# LED_Driver.net
KiCad netlist of a schematic drawn in Altium Designer
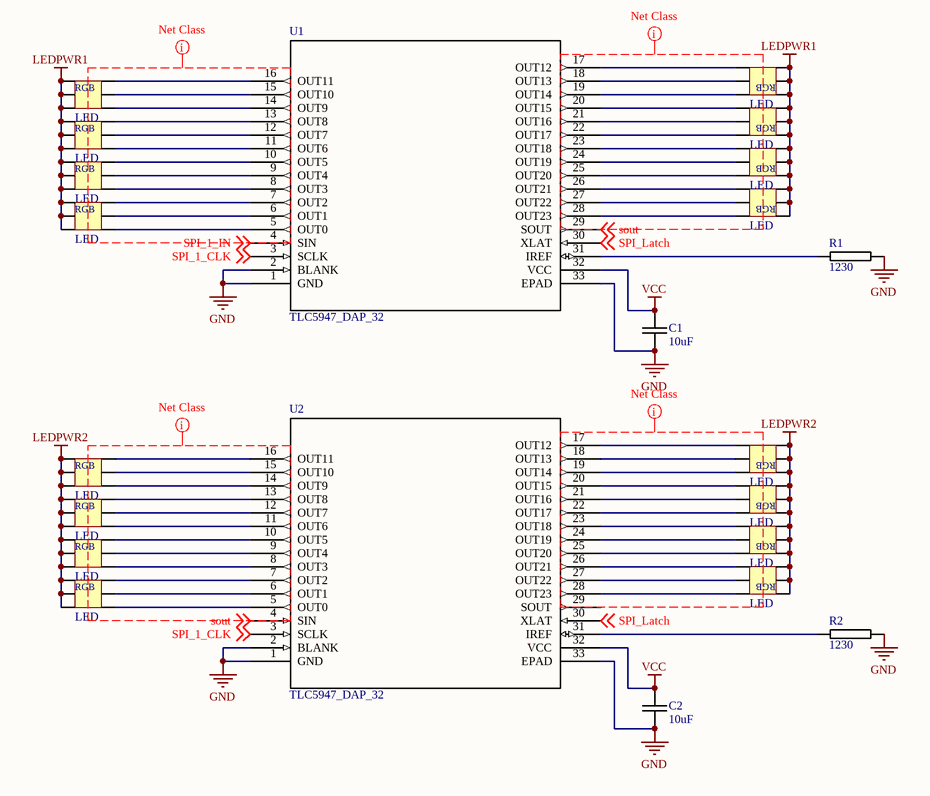
[diagram p0: LED Driver.SchDoc]

(export (version "E")
  (design (tool "Eeschema 10.0.6"))
  (components
    (comp (ref "C1")
      (value "10uF")
      (footprint "0603C-GENERIC")
      (description "CAPACITOR 0603 CERAMIC")
      (fields
        (field (name "MANUFACTURER PART NUMBER") "C1608X5R0J106M")
        (field (name "MANUFACTURER") "TDK Corporation")
      )
      (libsource (lib "vh_altium_library") (part "0603C-10UF-10V-X5R-TDK"))
    )
    (comp (ref "C2")
      (value "10uF")
      (footprint "0603C-GENERIC")
      (description "CAPACITOR 0603 CERAMIC")
      (fields
        (field (name "MANUFACTURER PART NUMBER") "C1608X5R0J106M")
        (field (name "MANUFACTURER") "TDK Corporation")
      )
      (libsource (lib "vh_altium_library") (part "0603C-10UF-10V-X5R-TDK"))
    )
    (comp (ref "D1") (value "LED") (footprint "LED-TRICOLOR-5050") (libsource (lib "") (part "RGB LED_1")))
    (comp (ref "D2")
      (value "LED")
      (footprint "LED-TRICOLOR-5050")
      (libsource (lib "2014-04-10_10-38-29") (part "RGB LED"))
    )
    (comp (ref "D3") (value "LED") (footprint "LED-TRICOLOR-5050") (libsource (lib "") (part "RGB LED_1")))
    (comp (ref "D4")
      (value "LED")
      (footprint "LED-TRICOLOR-5050")
      (libsource (lib "2014-04-10_10-38-29") (part "RGB LED"))
    )
    (comp (ref "D5") (value "LED") (footprint "LED-TRICOLOR-5050") (libsource (lib "") (part "RGB LED_1")))
    (comp (ref "D6")
      (value "LED")
      (footprint "LED-TRICOLOR-5050")
      (libsource (lib "2014-04-10_10-38-29") (part "RGB LED"))
    )
    (comp (ref "D7") (value "LED") (footprint "LED-TRICOLOR-5050") (libsource (lib "") (part "RGB LED_1")))
    (comp (ref "D8")
      (value "LED")
      (footprint "LED-TRICOLOR-5050")
      (libsource (lib "2014-04-10_10-38-29") (part "RGB LED"))
    )
    (comp (ref "D9") (value "LED") (footprint "LED-TRICOLOR-5050") (libsource (lib "") (part "RGB LED_1")))
    (comp (ref "D10")
      (value "LED")
      (footprint "LED-TRICOLOR-5050")
      (libsource (lib "2014-04-10_10-38-29") (part "RGB LED"))
    )
    (comp (ref "D11") (value "LED") (footprint "LED-TRICOLOR-5050") (libsource (lib "") (part "RGB LED_1")))
    (comp (ref "D12")
      (value "LED")
      (footprint "LED-TRICOLOR-5050")
      (libsource (lib "2014-04-10_10-38-29") (part "RGB LED"))
    )
    (comp (ref "D13") (value "LED") (footprint "LED-TRICOLOR-5050") (libsource (lib "") (part "RGB LED_1")))
    (comp (ref "D14")
      (value "LED")
      (footprint "LED-TRICOLOR-5050")
      (libsource (lib "2014-04-10_10-38-29") (part "RGB LED"))
    )
    (comp (ref "D15") (value "LED") (footprint "LED-TRICOLOR-5050") (libsource (lib "") (part "RGB LED_1")))
    (comp (ref "D16")
      (value "LED")
      (footprint "LED-TRICOLOR-5050")
      (libsource (lib "2014-04-10_10-38-29") (part "RGB LED"))
    )
    (comp (ref "R1")
      (value "1230")
      (footprint "0603R-TBD")
      (description "RESISTOR 0603 VALUE TO BE DETERMINED")
      (libsource (lib "vh_altium_library") (part "0603R-TBD"))
    )
    (comp (ref "R2")
      (value "1230")
      (footprint "0603R-TBD")
      (description "RESISTOR 0603 VALUE TO BE DETERMINED")
      (libsource (lib "vh_altium_library") (part "0603R-TBD"))
    )
    (comp (ref "U1")
      (value "TLC5947_DAP_32")
      (footprint "DAP32_4P36X4P11")
      (description "Imported")
      (fields
        (field (name "MANUFACTURER_PART_NUMBER") "tlc5947_dap_32")
        (field (name "GENERIC_PART_NUMBER") "TLC5947")
      )
      (libsource (lib "2014-04-10_10-38-29") (part "TLC5947_DAP_32"))
    )
    (comp (ref "U2")
      (value "TLC5947_DAP_32")
      (footprint "DAP32_4P36X4P11")
      (description "Imported")
      (fields
        (field (name "MANUFACTURER_PART_NUMBER") "tlc5947_dap_32")
        (field (name "GENERIC_PART_NUMBER") "TLC5947")
      )
      (libsource (lib "2014-04-10_10-38-29") (part "TLC5947_DAP_32"))
    )
  )
  (nets
    (net (code "1") (name "GND") (class "Default")
      (node (ref "C1") (pin "2") (pintype "passive"))
      (node (ref "C2") (pin "2") (pintype "passive"))
      (node (ref "R1") (pin "2") (pintype "passive"))
      (node (ref "R2") (pin "2") (pintype "passive"))
      (node (ref "U1") (pin "1") (pinfunction "GND_1") (pintype "power_in"))
      (node (ref "U1") (pin "2") (pinfunction "BLANK_2") (pintype "input"))
      (node (ref "U1") (pin "33") (pinfunction "EPAD_33") (pintype "passive"))
      (node (ref "U2") (pin "1") (pinfunction "GND_1") (pintype "power_in"))
      (node (ref "U2") (pin "2") (pinfunction "BLANK_2") (pintype "input"))
      (node (ref "U2") (pin "33") (pinfunction "EPAD_33") (pintype "passive"))
    )
    (net (code "2") (name "LEDPWR1") (class "Default")
      (node (ref "D1") (pin "1") (pinfunction "CB_1") (pintype "passive"))
      (node (ref "D1") (pin "2") (pinfunction "CR_2") (pintype "passive"))
      (node (ref "D1") (pin "3") (pinfunction "CG_3") (pintype "passive"))
      (node (ref "D2") (pin "1") (pinfunction "CB_1") (pintype "passive"))
      (node (ref "D2") (pin "2") (pinfunction "CR_2") (pintype "passive"))
      (node (ref "D2") (pin "3") (pinfunction "CG_3") (pintype "passive"))
      (node (ref "D3") (pin "1") (pinfunction "CB_1") (pintype "passive"))
      (node (ref "D3") (pin "2") (pinfunction "CR_2") (pintype "passive"))
      (node (ref "D3") (pin "3") (pinfunction "CG_3") (pintype "passive"))
      (node (ref "D4") (pin "1") (pinfunction "CB_1") (pintype "passive"))
      (node (ref "D4") (pin "2") (pinfunction "CR_2") (pintype "passive"))
      (node (ref "D4") (pin "3") (pinfunction "CG_3") (pintype "passive"))
      (node (ref "D5") (pin "1") (pinfunction "CB_1") (pintype "passive"))
      (node (ref "D5") (pin "2") (pinfunction "CR_2") (pintype "passive"))
      (node (ref "D5") (pin "3") (pinfunction "CG_3") (pintype "passive"))
      (node (ref "D6") (pin "1") (pinfunction "CB_1") (pintype "passive"))
      (node (ref "D6") (pin "2") (pinfunction "CR_2") (pintype "passive"))
      (node (ref "D6") (pin "3") (pinfunction "CG_3") (pintype "passive"))
      (node (ref "D7") (pin "1") (pinfunction "CB_1") (pintype "passive"))
      (node (ref "D7") (pin "2") (pinfunction "CR_2") (pintype "passive"))
      (node (ref "D7") (pin "3") (pinfunction "CG_3") (pintype "passive"))
      (node (ref "D8") (pin "1") (pinfunction "CB_1") (pintype "passive"))
      (node (ref "D8") (pin "2") (pinfunction "CR_2") (pintype "passive"))
      (node (ref "D8") (pin "3") (pinfunction "CG_3") (pintype "passive"))
    )
    (net (code "3") (name "LEDPWR2") (class "Default")
      (node (ref "D10") (pin "1") (pinfunction "CB_1") (pintype "passive"))
      (node (ref "D10") (pin "2") (pinfunction "CR_2") (pintype "passive"))
      (node (ref "D10") (pin "3") (pinfunction "CG_3") (pintype "passive"))
      (node (ref "D11") (pin "1") (pinfunction "CB_1") (pintype "passive"))
      (node (ref "D11") (pin "2") (pinfunction "CR_2") (pintype "passive"))
      (node (ref "D11") (pin "3") (pinfunction "CG_3") (pintype "passive"))
      (node (ref "D12") (pin "1") (pinfunction "CB_1") (pintype "passive"))
      (node (ref "D12") (pin "2") (pinfunction "CR_2") (pintype "passive"))
      (node (ref "D12") (pin "3") (pinfunction "CG_3") (pintype "passive"))
      (node (ref "D13") (pin "1") (pinfunction "CB_1") (pintype "passive"))
      (node (ref "D13") (pin "2") (pinfunction "CR_2") (pintype "passive"))
      (node (ref "D13") (pin "3") (pinfunction "CG_3") (pintype "passive"))
      (node (ref "D14") (pin "1") (pinfunction "CB_1") (pintype "passive"))
      (node (ref "D14") (pin "2") (pinfunction "CR_2") (pintype "passive"))
      (node (ref "D14") (pin "3") (pinfunction "CG_3") (pintype "passive"))
      (node (ref "D15") (pin "1") (pinfunction "CB_1") (pintype "passive"))
      (node (ref "D15") (pin "2") (pinfunction "CR_2") (pintype "passive"))
      (node (ref "D15") (pin "3") (pinfunction "CG_3") (pintype "passive"))
      (node (ref "D16") (pin "1") (pinfunction "CB_1") (pintype "passive"))
      (node (ref "D16") (pin "2") (pinfunction "CR_2") (pintype "passive"))
      (node (ref "D16") (pin "3") (pinfunction "CG_3") (pintype "passive"))
      (node (ref "D9") (pin "1") (pinfunction "CB_1") (pintype "passive"))
      (node (ref "D9") (pin "2") (pinfunction "CR_2") (pintype "passive"))
      (node (ref "D9") (pin "3") (pinfunction "CG_3") (pintype "passive"))
    )
    (net (code "4") (name "Net-(D1-AB)") (class "Default")
      (node (ref "D1") (pin "4") (pinfunction "AB_4") (pintype "passive"))
      (node (ref "U1") (pin "19") (pinfunction "OUT14_19") (pintype "output"))
    )
    (net (code "5") (name "Net-(D1-AG)") (class "Default")
      (node (ref "D1") (pin "6") (pinfunction "AG_6") (pintype "passive"))
      (node (ref "U1") (pin "17") (pinfunction "OUT12_17") (pintype "output"))
    )
    (net (code "6") (name "Net-(D1-AR)") (class "Default")
      (node (ref "D1") (pin "5") (pinfunction "AR_5") (pintype "passive"))
      (node (ref "U1") (pin "18") (pinfunction "OUT13_18") (pintype "output"))
    )
    (net (code "7") (name "Net-(D2-AB)") (class "Default")
      (node (ref "D2") (pin "4") (pinfunction "AB_4") (pintype "passive"))
      (node (ref "U1") (pin "16") (pinfunction "OUT11_16") (pintype "output"))
    )
    (net (code "8") (name "Net-(D2-AG)") (class "Default")
      (node (ref "D2") (pin "6") (pinfunction "AG_6") (pintype "passive"))
      (node (ref "U1") (pin "14") (pinfunction "OUT9_14") (pintype "output"))
    )
    (net (code "9") (name "Net-(D2-AR)") (class "Default")
      (node (ref "D2") (pin "5") (pinfunction "AR_5") (pintype "passive"))
      (node (ref "U1") (pin "15") (pinfunction "OUT10_15") (pintype "output"))
    )
    (net (code "10") (name "Net-(D3-AB)") (class "Default")
      (node (ref "D3") (pin "4") (pinfunction "AB_4") (pintype "passive"))
      (node (ref "U1") (pin "22") (pinfunction "OUT17_22") (pintype "output"))
    )
    (net (code "11") (name "Net-(D3-AG)") (class "Default")
      (node (ref "D3") (pin "6") (pinfunction "AG_6") (pintype "passive"))
      (node (ref "U1") (pin "20") (pinfunction "OUT15_20") (pintype "output"))
    )
    (net (code "12") (name "Net-(D3-AR)") (class "Default")
      (node (ref "D3") (pin "5") (pinfunction "AR_5") (pintype "passive"))
      (node (ref "U1") (pin "21") (pinfunction "OUT16_21") (pintype "output"))
    )
    (net (code "13") (name "Net-(D4-AB)") (class "Default")
      (node (ref "D4") (pin "4") (pinfunction "AB_4") (pintype "passive"))
      (node (ref "U1") (pin "13") (pinfunction "OUT8_13") (pintype "output"))
    )
    (net (code "14") (name "Net-(D4-AG)") (class "Default")
      (node (ref "D4") (pin "6") (pinfunction "AG_6") (pintype "passive"))
      (node (ref "U1") (pin "11") (pinfunction "OUT6_11") (pintype "output"))
    )
    (net (code "15") (name "Net-(D4-AR)") (class "Default")
      (node (ref "D4") (pin "5") (pinfunction "AR_5") (pintype "passive"))
      (node (ref "U1") (pin "12") (pinfunction "OUT7_12") (pintype "output"))
    )
    (net (code "16") (name "Net-(D5-AB)") (class "Default")
      (node (ref "D5") (pin "4") (pinfunction "AB_4") (pintype "passive"))
      (node (ref "U1") (pin "25") (pinfunction "OUT20_25") (pintype "output"))
    )
    (net (code "17") (name "Net-(D5-AG)") (class "Default")
      (node (ref "D5") (pin "6") (pinfunction "AG_6") (pintype "passive"))
      (node (ref "U1") (pin "23") (pinfunction "OUT18_23") (pintype "output"))
    )
    (net (code "18") (name "Net-(D5-AR)") (class "Default")
      (node (ref "D5") (pin "5") (pinfunction "AR_5") (pintype "passive"))
      (node (ref "U1") (pin "24") (pinfunction "OUT19_24") (pintype "output"))
    )
    (net (code "19") (name "Net-(D6-AB)") (class "Default")
      (node (ref "D6") (pin "4") (pinfunction "AB_4") (pintype "passive"))
      (node (ref "U1") (pin "10") (pinfunction "OUT5_10") (pintype "output"))
    )
    (net (code "20") (name "Net-(D6-AG)") (class "Default")
      (node (ref "D6") (pin "6") (pinfunction "AG_6") (pintype "passive"))
      (node (ref "U1") (pin "8") (pinfunction "OUT3_8") (pintype "output"))
    )
    (net (code "21") (name "Net-(D6-AR)") (class "Default")
      (node (ref "D6") (pin "5") (pinfunction "AR_5") (pintype "passive"))
      (node (ref "U1") (pin "9") (pinfunction "OUT4_9") (pintype "output"))
    )
    (net (code "22") (name "Net-(D7-AB)") (class "Default")
      (node (ref "D7") (pin "4") (pinfunction "AB_4") (pintype "passive"))
      (node (ref "U1") (pin "28") (pinfunction "OUT23_28") (pintype "output"))
    )
    (net (code "23") (name "Net-(D7-AG)") (class "Default")
      (node (ref "D7") (pin "6") (pinfunction "AG_6") (pintype "passive"))
      (node (ref "U1") (pin "26") (pinfunction "OUT21_26") (pintype "output"))
    )
    (net (code "24") (name "Net-(D7-AR)") (class "Default")
      (node (ref "D7") (pin "5") (pinfunction "AR_5") (pintype "passive"))
      (node (ref "U1") (pin "27") (pinfunction "OUT22_27") (pintype "output"))
    )
    (net (code "25") (name "Net-(D8-AB)") (class "Default")
      (node (ref "D8") (pin "4") (pinfunction "AB_4") (pintype "passive"))
      (node (ref "U1") (pin "7") (pinfunction "OUT2_7") (pintype "output"))
    )
    (net (code "26") (name "Net-(D8-AG)") (class "Default")
      (node (ref "D8") (pin "6") (pinfunction "AG_6") (pintype "passive"))
      (node (ref "U1") (pin "5") (pinfunction "OUT0_5") (pintype "output"))
    )
    (net (code "27") (name "Net-(D8-AR)") (class "Default")
      (node (ref "D8") (pin "5") (pinfunction "AR_5") (pintype "passive"))
      (node (ref "U1") (pin "6") (pinfunction "OUT1_6") (pintype "output"))
    )
    (net (code "28") (name "Net-(D9-AB)") (class "Default")
      (node (ref "D9") (pin "4") (pinfunction "AB_4") (pintype "passive"))
      (node (ref "U2") (pin "19") (pinfunction "OUT14_19") (pintype "output"))
    )
    (net (code "29") (name "Net-(D9-AG)") (class "Default")
      (node (ref "D9") (pin "6") (pinfunction "AG_6") (pintype "passive"))
      (node (ref "U2") (pin "17") (pinfunction "OUT12_17") (pintype "output"))
    )
    (net (code "30") (name "Net-(D9-AR)") (class "Default")
      (node (ref "D9") (pin "5") (pinfunction "AR_5") (pintype "passive"))
      (node (ref "U2") (pin "18") (pinfunction "OUT13_18") (pintype "output"))
    )
    (net (code "31") (name "Net-(D10-AB)") (class "Default")
      (node (ref "D10") (pin "4") (pinfunction "AB_4") (pintype "passive"))
      (node (ref "U2") (pin "16") (pinfunction "OUT11_16") (pintype "output"))
    )
    (net (code "32") (name "Net-(D10-AG)") (class "Default")
      (node (ref "D10") (pin "6") (pinfunction "AG_6") (pintype "passive"))
      (node (ref "U2") (pin "14") (pinfunction "OUT9_14") (pintype "output"))
    )
    (net (code "33") (name "Net-(D10-AR)") (class "Default")
      (node (ref "D10") (pin "5") (pinfunction "AR_5") (pintype "passive"))
      (node (ref "U2") (pin "15") (pinfunction "OUT10_15") (pintype "output"))
    )
    (net (code "34") (name "Net-(D11-AB)") (class "Default")
      (node (ref "D11") (pin "4") (pinfunction "AB_4") (pintype "passive"))
      (node (ref "U2") (pin "22") (pinfunction "OUT17_22") (pintype "output"))
    )
    (net (code "35") (name "Net-(D11-AG)") (class "Default")
      (node (ref "D11") (pin "6") (pinfunction "AG_6") (pintype "passive"))
      (node (ref "U2") (pin "20") (pinfunction "OUT15_20") (pintype "output"))
    )
    (net (code "36") (name "Net-(D11-AR)") (class "Default")
      (node (ref "D11") (pin "5") (pinfunction "AR_5") (pintype "passive"))
      (node (ref "U2") (pin "21") (pinfunction "OUT16_21") (pintype "output"))
    )
    (net (code "37") (name "Net-(D12-AB)") (class "Default")
      (node (ref "D12") (pin "4") (pinfunction "AB_4") (pintype "passive"))
      (node (ref "U2") (pin "13") (pinfunction "OUT8_13") (pintype "output"))
    )
    (net (code "38") (name "Net-(D12-AG)") (class "Default")
      (node (ref "D12") (pin "6") (pinfunction "AG_6") (pintype "passive"))
      (node (ref "U2") (pin "11") (pinfunction "OUT6_11") (pintype "output"))
    )
    (net (code "39") (name "Net-(D12-AR)") (class "Default")
      (node (ref "D12") (pin "5") (pinfunction "AR_5") (pintype "passive"))
      (node (ref "U2") (pin "12") (pinfunction "OUT7_12") (pintype "output"))
    )
    (net (code "40") (name "Net-(D13-AB)") (class "Default")
      (node (ref "D13") (pin "4") (pinfunction "AB_4") (pintype "passive"))
      (node (ref "U2") (pin "25") (pinfunction "OUT20_25") (pintype "output"))
    )
    (net (code "41") (name "Net-(D13-AG)") (class "Default")
      (node (ref "D13") (pin "6") (pinfunction "AG_6") (pintype "passive"))
      (node (ref "U2") (pin "23") (pinfunction "OUT18_23") (pintype "output"))
    )
    (net (code "42") (name "Net-(D13-AR)") (class "Default")
      (node (ref "D13") (pin "5") (pinfunction "AR_5") (pintype "passive"))
      (node (ref "U2") (pin "24") (pinfunction "OUT19_24") (pintype "output"))
    )
    (net (code "43") (name "Net-(D14-AB)") (class "Default")
      (node (ref "D14") (pin "4") (pinfunction "AB_4") (pintype "passive"))
      (node (ref "U2") (pin "10") (pinfunction "OUT5_10") (pintype "output"))
    )
    (net (code "44") (name "Net-(D14-AG)") (class "Default")
      (node (ref "D14") (pin "6") (pinfunction "AG_6") (pintype "passive"))
      (node (ref "U2") (pin "8") (pinfunction "OUT3_8") (pintype "output"))
    )
    (net (code "45") (name "Net-(D14-AR)") (class "Default")
      (node (ref "D14") (pin "5") (pinfunction "AR_5") (pintype "passive"))
      (node (ref "U2") (pin "9") (pinfunction "OUT4_9") (pintype "output"))
    )
    (net (code "46") (name "Net-(D15-AB)") (class "Default")
      (node (ref "D15") (pin "4") (pinfunction "AB_4") (pintype "passive"))
      (node (ref "U2") (pin "28") (pinfunction "OUT23_28") (pintype "output"))
    )
    (net (code "47") (name "Net-(D15-AG)") (class "Default")
      (node (ref "D15") (pin "6") (pinfunction "AG_6") (pintype "passive"))
      (node (ref "U2") (pin "26") (pinfunction "OUT21_26") (pintype "output"))
    )
    (net (code "48") (name "Net-(D15-AR)") (class "Default")
      (node (ref "D15") (pin "5") (pinfunction "AR_5") (pintype "passive"))
      (node (ref "U2") (pin "27") (pinfunction "OUT22_27") (pintype "output"))
    )
    (net (code "49") (name "Net-(D16-AB)") (class "Default")
      (node (ref "D16") (pin "4") (pinfunction "AB_4") (pintype "passive"))
      (node (ref "U2") (pin "7") (pinfunction "OUT2_7") (pintype "output"))
    )
    (net (code "50") (name "Net-(D16-AG)") (class "Default")
      (node (ref "D16") (pin "6") (pinfunction "AG_6") (pintype "passive"))
      (node (ref "U2") (pin "5") (pinfunction "OUT0_5") (pintype "output"))
    )
    (net (code "51") (name "Net-(D16-AR)") (class "Default")
      (node (ref "D16") (pin "5") (pinfunction "AR_5") (pintype "passive"))
      (node (ref "U2") (pin "6") (pinfunction "OUT1_6") (pintype "output"))
    )
    (net (code "52") (name "Net-(U1-IREF)") (class "Default")
      (node (ref "R1") (pin "1") (pintype "passive"))
      (node (ref "U1") (pin "31") (pinfunction "IREF_31") (pintype "bidirectional"))
    )
    (net (code "53") (name "Net-(U2-IREF)") (class "Default")
      (node (ref "R2") (pin "1") (pintype "passive"))
      (node (ref "U2") (pin "31") (pinfunction "IREF_31") (pintype "bidirectional"))
    )
    (net (code "54") (name "SPI_1_CLK") (class "Default")
      (node (ref "U1") (pin "3") (pinfunction "SCLK_3") (pintype "input"))
      (node (ref "U2") (pin "3") (pinfunction "SCLK_3") (pintype "input"))
    )
    (net (code "55") (name "SPI_1_IN") (class "Default")
      (node (ref "U1") (pin "4") (pinfunction "SIN_4") (pintype "input"))
    )
    (net (code "56") (name "SPI_Latch") (class "Default")
      (node (ref "U1") (pin "30") (pinfunction "XLAT_30") (pintype "input"))
      (node (ref "U2") (pin "30") (pinfunction "XLAT_30") (pintype "input"))
    )
    (net (code "57") (name "VCC") (class "Default")
      (node (ref "C1") (pin "1") (pintype "passive"))
      (node (ref "C2") (pin "1") (pintype "passive"))
      (node (ref "U1") (pin "32") (pinfunction "VCC_32") (pintype "power_in"))
      (node (ref "U2") (pin "32") (pinfunction "VCC_32") (pintype "power_in"))
    )
    (net (code "58") (name "sout") (class "Default")
      (node (ref "U1") (pin "29") (pinfunction "SOUT_29") (pintype "output"))
      (node (ref "U2") (pin "4") (pinfunction "SIN_4") (pintype "input"))
    )
    (net (code "59") (name "unconnected-(U2-SOUT-Pad29)") (class "Default")
      (node (ref "U2") (pin "29") (pinfunction "SOUT_29") (pintype "output"))
    )
  )
)
